# luabox.net
KiCad netlist of a schematic drawn in EasyEDA Pro
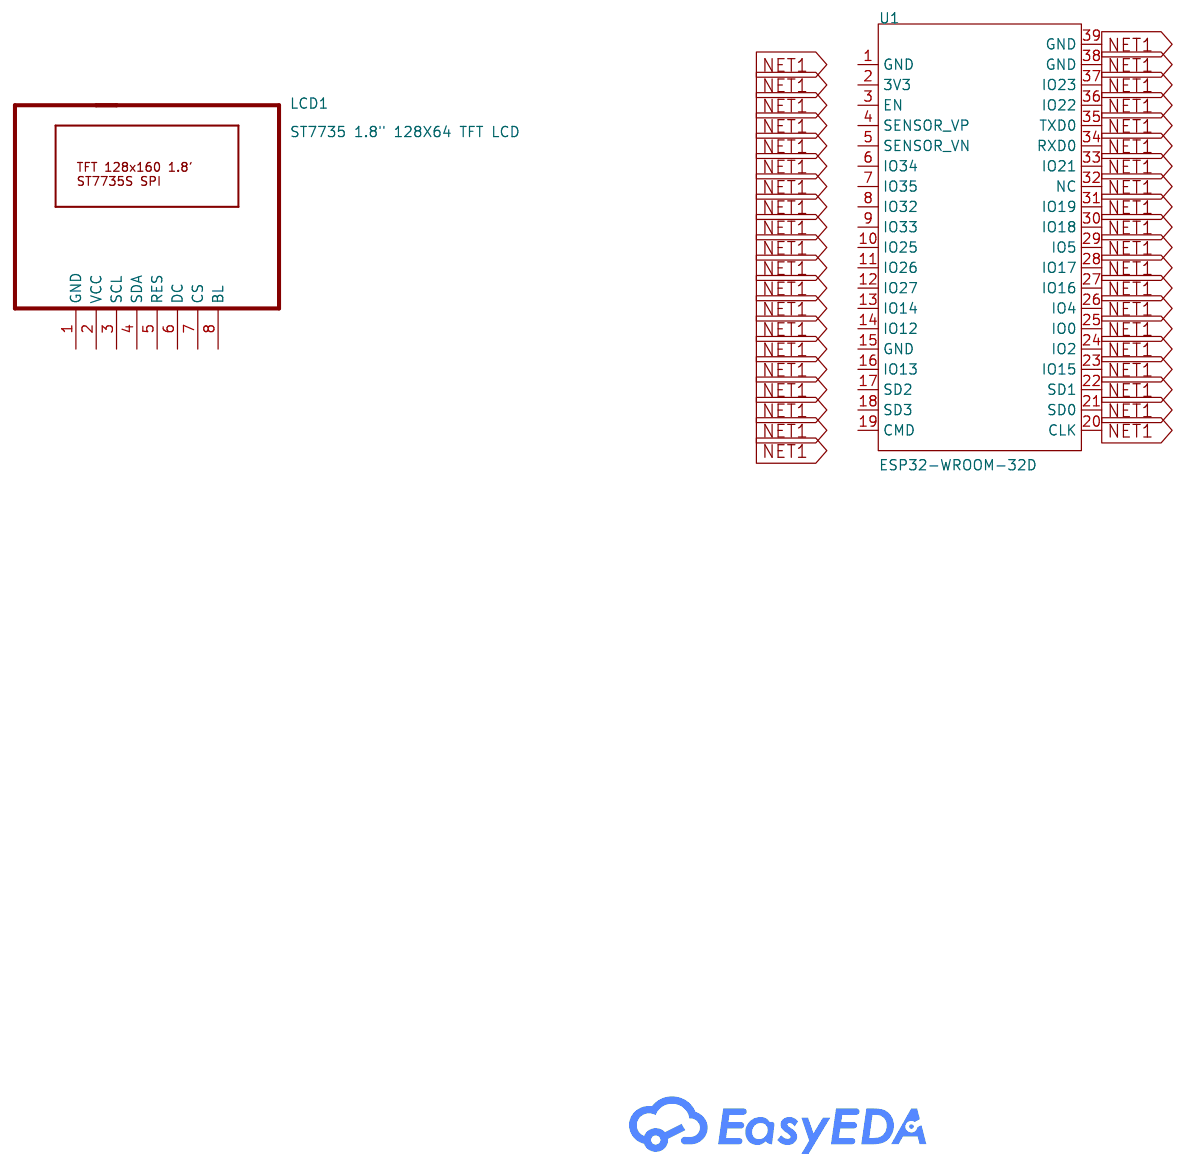
[diagram p0: schematic sheet]

(export (version "E")
  (design (tool "Eeschema 10.0.6"))
  (components
    (comp (ref "LCD1")
      (value "ST7735 1.8\" 128X64 TFT LCD")
      (libsource (lib "easyedapro") (part "ST7735 1.8&quot; 128X64 TFT LCD"))
    )
    (comp (ref "U1")
      (value "ESP32-WROOM-32D")
      (footprint "easyedapro:WIFIM-SMD_ESP32-WROOM-32D")
      (libsource (lib "easyedapro") (part "ESP32-WROOM-32D_C503588"))
    )
  )
  (nets
    (net (code "1") (name "NET1") (class "Default")
      (node (ref "U1") (pin "20") (pinfunction "CLK_20") (pintype "unspecified"))
      (node (ref "U1") (pin "21") (pinfunction "SD0_21") (pintype "unspecified"))
      (node (ref "U1") (pin "22") (pinfunction "SD1_22") (pintype "unspecified"))
      (node (ref "U1") (pin "23") (pinfunction "IO15_23") (pintype "unspecified"))
      (node (ref "U1") (pin "24") (pinfunction "IO2_24") (pintype "unspecified"))
      (node (ref "U1") (pin "25") (pinfunction "IO0_25") (pintype "unspecified"))
      (node (ref "U1") (pin "26") (pinfunction "IO4_26") (pintype "unspecified"))
      (node (ref "U1") (pin "27") (pinfunction "IO16_27") (pintype "unspecified"))
      (node (ref "U1") (pin "28") (pinfunction "IO17_28") (pintype "unspecified"))
      (node (ref "U1") (pin "29") (pinfunction "IO5_29") (pintype "unspecified"))
      (node (ref "U1") (pin "30") (pinfunction "IO18_30") (pintype "unspecified"))
      (node (ref "U1") (pin "31") (pinfunction "IO19_31") (pintype "unspecified"))
      (node (ref "U1") (pin "32") (pinfunction "NC_32") (pintype "unspecified"))
      (node (ref "U1") (pin "33") (pinfunction "IO21_33") (pintype "unspecified"))
      (node (ref "U1") (pin "34") (pinfunction "RXD0_34") (pintype "unspecified"))
      (node (ref "U1") (pin "35") (pinfunction "TXD0_35") (pintype "unspecified"))
      (node (ref "U1") (pin "36") (pinfunction "IO22_36") (pintype "unspecified"))
      (node (ref "U1") (pin "37") (pinfunction "IO23_37") (pintype "unspecified"))
      (node (ref "U1") (pin "38") (pinfunction "GND_38") (pintype "unspecified"))
      (node (ref "U1") (pin "39") (pinfunction "GND_39") (pintype "unspecified"))
    )
    (net (code "2") (name "unconnected-(LCD1-BL-Pad8)") (class "Default")
      (node (ref "LCD1") (pin "8") (pinfunction "BL_8") (pintype "input"))
    )
    (net (code "3") (name "unconnected-(LCD1-CS-Pad7)") (class "Default")
      (node (ref "LCD1") (pin "7") (pinfunction "CS_7") (pintype "unspecified"))
    )
    (net (code "4") (name "unconnected-(LCD1-DC-Pad6)") (class "Default")
      (node (ref "LCD1") (pin "6") (pinfunction "DC_6") (pintype "input"))
    )
    (net (code "5") (name "unconnected-(LCD1-GND-Pad1)") (class "Default")
      (node (ref "LCD1") (pin "1") (pinfunction "GND_1") (pintype "unspecified"))
    )
    (net (code "6") (name "unconnected-(LCD1-RES-Pad5)") (class "Default")
      (node (ref "LCD1") (pin "5") (pinfunction "RES_5") (pintype "input"))
    )
    (net (code "7") (name "unconnected-(LCD1-SCL-Pad3)") (class "Default")
      (node (ref "LCD1") (pin "3") (pinfunction "SCL_3") (pintype "input"))
    )
    (net (code "8") (name "unconnected-(LCD1-SDA-Pad4)") (class "Default")
      (node (ref "LCD1") (pin "4") (pinfunction "SDA_4") (pintype "input"))
    )
    (net (code "9") (name "unconnected-(LCD1-VCC-Pad2)") (class "Default")
      (node (ref "LCD1") (pin "2") (pinfunction "VCC_2") (pintype "output"))
    )
    (net (code "10") (name "unconnected-(U1-3V3-Pad2)") (class "Default")
      (node (ref "U1") (pin "2") (pinfunction "3V3_2") (pintype "unspecified"))
    )
    (net (code "11") (name "unconnected-(U1-CMD-Pad19)") (class "Default")
      (node (ref "U1") (pin "19") (pinfunction "CMD_19") (pintype "unspecified"))
    )
    (net (code "12") (name "unconnected-(U1-EN-Pad3)") (class "Default")
      (node (ref "U1") (pin "3") (pinfunction "EN_3") (pintype "unspecified"))
    )
    (net (code "13") (name "unconnected-(U1-GND-Pad1)") (class "Default")
      (node (ref "U1") (pin "1") (pinfunction "GND_1") (pintype "unspecified"))
    )
    (net (code "14") (name "unconnected-(U1-GND-Pad15)") (class "Default")
      (node (ref "U1") (pin "15") (pinfunction "GND_15") (pintype "unspecified"))
    )
    (net (code "15") (name "unconnected-(U1-IO12-Pad14)") (class "Default")
      (node (ref "U1") (pin "14") (pinfunction "IO12_14") (pintype "unspecified"))
    )
    (net (code "16") (name "unconnected-(U1-IO13-Pad16)") (class "Default")
      (node (ref "U1") (pin "16") (pinfunction "IO13_16") (pintype "unspecified"))
    )
    (net (code "17") (name "unconnected-(U1-IO14-Pad13)") (class "Default")
      (node (ref "U1") (pin "13") (pinfunction "IO14_13") (pintype "unspecified"))
    )
    (net (code "18") (name "unconnected-(U1-IO25-Pad10)") (class "Default")
      (node (ref "U1") (pin "10") (pinfunction "IO25_10") (pintype "unspecified"))
    )
    (net (code "19") (name "unconnected-(U1-IO26-Pad11)") (class "Default")
      (node (ref "U1") (pin "11") (pinfunction "IO26_11") (pintype "unspecified"))
    )
    (net (code "20") (name "unconnected-(U1-IO27-Pad12)") (class "Default")
      (node (ref "U1") (pin "12") (pinfunction "IO27_12") (pintype "unspecified"))
    )
    (net (code "21") (name "unconnected-(U1-IO32-Pad8)") (class "Default")
      (node (ref "U1") (pin "8") (pinfunction "IO32_8") (pintype "unspecified"))
    )
    (net (code "22") (name "unconnected-(U1-IO33-Pad9)") (class "Default")
      (node (ref "U1") (pin "9") (pinfunction "IO33_9") (pintype "unspecified"))
    )
    (net (code "23") (name "unconnected-(U1-IO34-Pad6)") (class "Default")
      (node (ref "U1") (pin "6") (pinfunction "IO34_6") (pintype "unspecified"))
    )
    (net (code "24") (name "unconnected-(U1-IO35-Pad7)") (class "Default")
      (node (ref "U1") (pin "7") (pinfunction "IO35_7") (pintype "unspecified"))
    )
    (net (code "25") (name "unconnected-(U1-SD2-Pad17)") (class "Default")
      (node (ref "U1") (pin "17") (pinfunction "SD2_17") (pintype "unspecified"))
    )
    (net (code "26") (name "unconnected-(U1-SD3-Pad18)") (class "Default")
      (node (ref "U1") (pin "18") (pinfunction "SD3_18") (pintype "unspecified"))
    )
    (net (code "27") (name "unconnected-(U1-SENSOR_VN-Pad5)") (class "Default")
      (node (ref "U1") (pin "5") (pinfunction "SENSOR_VN_5") (pintype "unspecified"))
    )
    (net (code "28") (name "unconnected-(U1-SENSOR_VP-Pad4)") (class "Default")
      (node (ref "U1") (pin "4") (pinfunction "SENSOR_VP_4") (pintype "unspecified"))
    )
  )
)
